# MCU_Display.net
KiCad netlist of a schematic drawn in Altium Designer
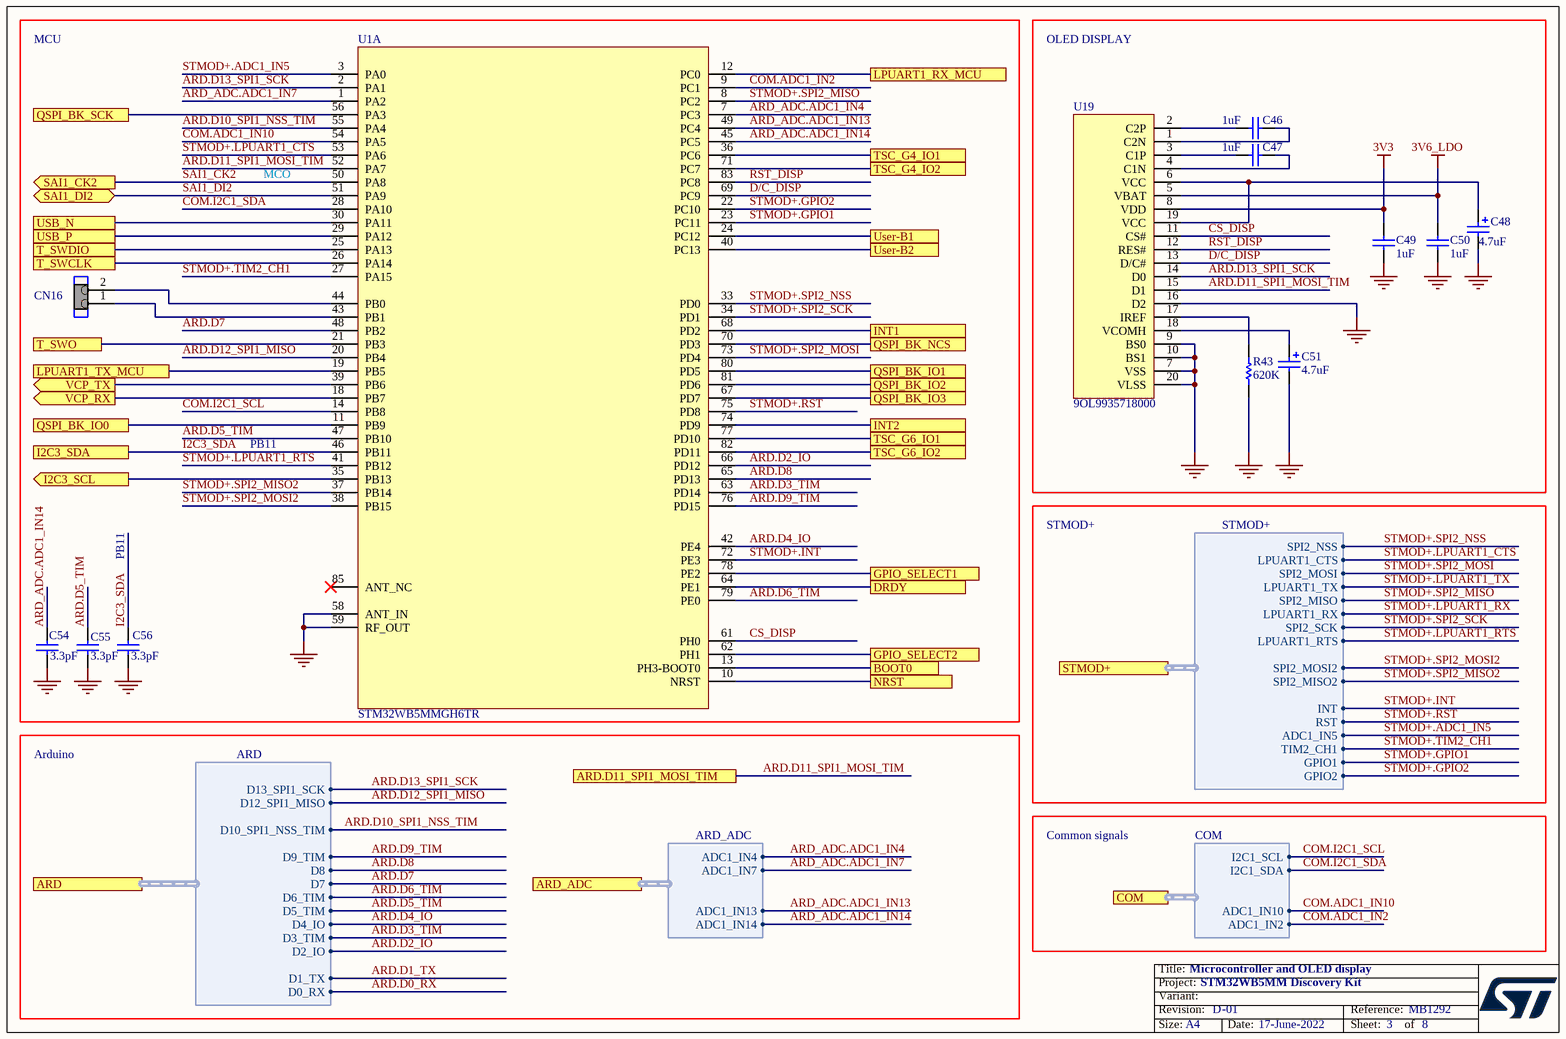
[diagram p0: MCU_Display.SchDoc]

(export (version "E")
  (design (tool "Eeschema 10.0.6"))
  (components
    (comp (ref "C46")
      (value "1uF")
      (footprint "C0603")
      (description "Capacitor, MLCC, 1uF, 16V, X5R, +/-10%, 0603, T=0,8mm")
      (fields
        (field (name "INTERNAL_PART_NUMBER") "MCD-00010")
        (field (name "MANUFACTURER_PART_NUMBER") "CC0603KRX5R7BB105")
      )
      (libsource (lib "MCD_PARTS_database") (part "Capacitor"))
    )
    (comp (ref "C47")
      (value "1uF")
      (footprint "C0603")
      (description "Capacitor, MLCC, 1uF, 16V, X5R, +/-10%, 0603, T=0,8mm")
      (fields
        (field (name "INTERNAL_PART_NUMBER") "MCD-00010")
        (field (name "MANUFACTURER_PART_NUMBER") "CC0603KRX5R7BB105")
      )
      (libsource (lib "MCD_PARTS_database") (part "Capacitor"))
    )
    (comp (ref "C48")
      (value "4.7uF")
      (footprint "CPOL_TAJ-A_1206_H180")
      (description "Capacitor, Tantalum, 4.7uF, 25V, 5.5ohms, 10%,pkg Type_A (3216 metric), T=1.6mm")
      (fields
        (field (name "INTERNAL_PART_NUMBER") "MCD-01043")
        (field (name "MANUFACTURER_PART_NUMBER") "293D475X9025A2TE3")
      )
      (libsource (lib "MCD_PARTS_database") (part "Cap_POL_TANA"))
    )
    (comp (ref "C49")
      (value "1uF")
      (footprint "C0603")
      (description "Capacitor, MLCC, 1uF, 16V, X5R, +/-10%, 0603, T=0,8mm")
      (fields
        (field (name "INTERNAL_PART_NUMBER") "MCD-00010")
        (field (name "MANUFACTURER_PART_NUMBER") "CC0603KRX5R7BB105")
      )
      (libsource (lib "MCD_PARTS_database") (part "Capacitor"))
    )
    (comp (ref "C50")
      (value "1uF")
      (footprint "C0603")
      (description "Capacitor, MLCC, 1uF, 16V, X5R, +/-10%, 0603, T=0,8mm")
      (fields
        (field (name "INTERNAL_PART_NUMBER") "MCD-00010")
        (field (name "MANUFACTURER_PART_NUMBER") "CC0603KRX5R7BB105")
      )
      (libsource (lib "MCD_PARTS_database") (part "Capacitor"))
    )
    (comp (ref "C51")
      (value "4.7uF")
      (footprint "CPOL_TAJ-A_1206_H180")
      (description "Capacitor, Tantalum, 4.7uF, 25V, 5.5ohms, 10%,pkg Type_A (3216 metric), T=1.6mm")
      (fields
        (field (name "INTERNAL_PART_NUMBER") "MCD-01043")
        (field (name "MANUFACTURER_PART_NUMBER") "293D475X9025A2TE3")
      )
      (libsource (lib "MCD_PARTS_database") (part "Cap_POL_TANA"))
    )
    (comp (ref "C54")
      (value "3.3pF")
      (footprint "C0201_H0P3")
      (description "Capacitor, MLCC, 3.3pF, 50V, NPO, +-0.05pF, 0201, T=0.3mm\".")
      (fields (field (name "INTERNAL_PART_NUMBER") "MCD-02284") (field (name "MANUFACTURER") "MURATA"))
      (libsource (lib "MCD_PARTS_database") (part "Capacitor"))
    )
    (comp (ref "C55")
      (value "3.3pF")
      (footprint "C0201_H0P3")
      (description "Capacitor, MLCC, 3.3pF, 50V, NPO, +-0.05pF, 0201, T=0.3mm\".")
      (fields (field (name "INTERNAL_PART_NUMBER") "MCD-02284") (field (name "MANUFACTURER") "MURATA"))
      (libsource (lib "MCD_PARTS_database") (part "Capacitor"))
    )
    (comp (ref "C56")
      (value "3.3pF")
      (footprint "C0201_H0P3")
      (description "Capacitor, MLCC, 3.3pF, 50V, NPO, +-0.05pF, 0201, T=0.3mm\".")
      (fields (field (name "INTERNAL_PART_NUMBER") "MCD-02284") (field (name "MANUFACTURER") "MURATA"))
      (libsource (lib "MCD_PARTS_database") (part "Capacitor"))
    )
    (comp (ref "CN16")
      (value "Jumper_Header1.27 2x1 Fitted")
      (footprint "CON_WP_707-2-02-2-20-00")
      (description "Header, 2x1, 1.27mm, RA, TH, T=3.05mm/1.27mm")
      (fields (field (name "INTERNAL_PART_NUMBER") "MCD-01428") (field (name "MANUFACTURER") "W&P PRODUCTS"))
      (libsource (lib "MCD_PARTS_database") (part "Jumper_Header1.27 2x1 Fitted"))
    )
    (comp (ref "R43")
      (value "620K")
      (footprint "R0603")
      (description "Resistor,620K,0603,1%,1/10W")
      (fields
        (field (name "INTERNAL_PART_NUMBER") "MCD-00506")
        (field (name "MANUFACTURER_PART_NUMBER") "RC0603FR-07620KL")
      )
      (libsource (lib "MCD_PARTS_database") (part "Resistor"))
    )
    (comp (ref "U1")
      (value "STM32WB5MMGH6TR")
      (footprint "MOD_DORY_STM_86P_7P3X11_H1P342")
      (description "STM32 BLE module based on STM32WB55")
      (fields
        (field (name "INTERNAL_PART_NUMBER") "MCD-01965")
        (field (name "MANUFACTURER") "STMICROELECTRONICS")
      )
      (libsource (lib "MCD_PARTS_database") (part "STM32WB5MMGH6TR"))
    )
    (comp (ref "U19")
      (value "9OL9935718000")
      (footprint "OLED_RITDISPLAY_9OL9935718000")
      (description "128*64 Dots 20-pin OLED display")
      (fields (field (name "INTERNAL_PART_NUMBER") "MCD-01925") (field (name "MANUFACTURER") "RITDISPLAY"))
      (libsource (lib "MCD_PARTS_database") (part "OLED_RITDISPLAY_9OL9935718000"))
    )
  )
  (nets
    (net (code "7") (name "/ARD.D2_IO") (class "Default")
      (node (ref "U1") (pin "66") (pinfunction "PD12_66") (pintype "passive"))
    )
    (net (code "8") (name "/ARD.D3_TIM") (class "Default")
      (node (ref "U1") (pin "63") (pinfunction "PD14_63") (pintype "passive"))
    )
    (net (code "9") (name "/ARD.D4_IO") (class "Default")
      (node (ref "U1") (pin "42") (pinfunction "PE4_42") (pintype "passive"))
    )
    (net (code "10") (name "/ARD.D5_TIM") (class "Default")
      (node (ref "C55") (pin "2") (pinfunction "2_2") (pintype "passive"))
      (node (ref "U1") (pin "47") (pinfunction "PB10_47") (pintype "passive"))
    )
    (net (code "11") (name "/ARD.D6_TIM") (class "Default")
      (node (ref "U1") (pin "79") (pinfunction "PE0_79") (pintype "passive"))
    )
    (net (code "12") (name "/ARD.D7") (class "Default")
      (node (ref "U1") (pin "48") (pinfunction "PB2_48") (pintype "passive"))
    )
    (net (code "13") (name "/ARD.D8") (class "Default")
      (node (ref "U1") (pin "65") (pinfunction "PD13_65") (pintype "passive"))
    )
    (net (code "14") (name "/ARD.D9_TIM") (class "Default")
      (node (ref "U1") (pin "76") (pinfunction "PD15_76") (pintype "passive"))
    )
    (net (code "15") (name "/ARD.D10_SPI1_NSS_TIM") (class "Default")
      (node (ref "U1") (pin "55") (pinfunction "PA4_55") (pintype "passive"))
    )
    (net (code "16") (name "/ARD.D11_SPI1_MOSI_TIM") (class "Default")
      (node (ref "U1") (pin "52") (pinfunction "PA7_52") (pintype "passive"))
      (node (ref "U19") (pin "15") (pinfunction "D1_15") (pintype "passive"))
    )
    (net (code "17") (name "/ARD.D12_SPI1_MISO") (class "Default")
      (node (ref "U1") (pin "20") (pinfunction "PB4_20") (pintype "passive"))
    )
    (net (code "18") (name "/ARD.D13_SPI1_SCK") (class "Default")
      (node (ref "U1") (pin "2") (pinfunction "PA1_2") (pintype "passive"))
      (node (ref "U19") (pin "14") (pinfunction "D0_14") (pintype "passive"))
    )
    (net (code "19") (name "/ARD_ADC.ADC1_IN4") (class "Default")
      (node (ref "U1") (pin "7") (pinfunction "PC3_7") (pintype "passive"))
    )
    (net (code "20") (name "/ARD_ADC.ADC1_IN7") (class "Default")
      (node (ref "U1") (pin "1") (pinfunction "PA2_1") (pintype "passive"))
    )
    (net (code "21") (name "/ARD_ADC.ADC1_IN13") (class "Default")
      (node (ref "U1") (pin "49") (pinfunction "PC4_49") (pintype "passive"))
    )
    (net (code "22") (name "/ARD_ADC.ADC1_IN14") (class "Default")
      (node (ref "C54") (pin "1") (pinfunction "1_1") (pintype "passive"))
      (node (ref "U1") (pin "45") (pinfunction "PC5_45") (pintype "passive"))
    )
    (net (code "23") (name "/BOOT0") (class "Default")
      (node (ref "U1") (pin "13") (pinfunction "PH3-BOOT0_13") (pintype "passive"))
    )
    (net (code "24") (name "/COM.ADC1_IN2") (class "Default")
      (node (ref "U1") (pin "9") (pinfunction "PC1_9") (pintype "passive"))
    )
    (net (code "25") (name "/COM.ADC1_IN10") (class "Default")
      (node (ref "U1") (pin "54") (pinfunction "PA5_54") (pintype "passive"))
    )
    (net (code "26") (name "/COM.I2C1_SCL") (class "Default")
      (node (ref "U1") (pin "14") (pinfunction "PB8_14") (pintype "passive"))
    )
    (net (code "27") (name "/COM.I2C1_SDA") (class "Default")
      (node (ref "U1") (pin "28") (pinfunction "PA10_28") (pintype "passive"))
    )
    (net (code "28") (name "/CS_DISP") (class "Default")
      (node (ref "U1") (pin "61") (pinfunction "PH0_61") (pintype "passive"))
      (node (ref "U19") (pin "11") (pinfunction "CS#_11") (pintype "passive"))
    )
    (net (code "29") (name "/DRDY") (class "Default")
      (node (ref "U1") (pin "64") (pinfunction "PE1_64") (pintype "passive"))
    )
    (net (code "30") (name "/D{slash}C_DISP") (class "Default")
      (node (ref "U1") (pin "69") (pinfunction "PC9_69") (pintype "passive"))
      (node (ref "U19") (pin "13") (pinfunction "D/C#_13") (pintype "passive"))
    )
    (net (code "31") (name "/GPIO_SELECT1") (class "Default")
      (node (ref "U1") (pin "78") (pinfunction "PE2_78") (pintype "passive"))
    )
    (net (code "32") (name "/GPIO_SELECT2") (class "Default")
      (node (ref "U1") (pin "62") (pinfunction "PH1_62") (pintype "passive"))
    )
    (net (code "33") (name "/I2C3_SCL") (class "Default")
      (node (ref "U1") (pin "35") (pinfunction "PB13_35") (pintype "passive"))
    )
    (net (code "34") (name "/I2C3_SDA") (class "Default")
      (node (ref "C56") (pin "2") (pinfunction "2_2") (pintype "passive"))
      (node (ref "U1") (pin "46") (pinfunction "PB11_46") (pintype "passive"))
    )
    (net (code "35") (name "/INT1") (class "Default")
      (node (ref "U1") (pin "68") (pinfunction "PD2_68") (pintype "passive"))
    )
    (net (code "36") (name "/INT2") (class "Default")
      (node (ref "U1") (pin "74") (pinfunction "PD9_74") (pintype "passive"))
    )
    (net (code "37") (name "/LPUART1_RX_MCU") (class "Default")
      (node (ref "U1") (pin "12") (pinfunction "PC0_12") (pintype "passive"))
    )
    (net (code "38") (name "/LPUART1_TX_MCU") (class "Default")
      (node (ref "U1") (pin "19") (pinfunction "PB5_19") (pintype "passive"))
    )
    (net (code "39") (name "/NRST") (class "Default")
      (node (ref "U1") (pin "10") (pinfunction "NRST_10") (pintype "passive"))
    )
    (net (code "40") (name "/QSPI_BK_IO0") (class "Default")
      (node (ref "U1") (pin "11") (pinfunction "PB9_11") (pintype "passive"))
    )
    (net (code "41") (name "/QSPI_BK_IO1") (class "Default")
      (node (ref "U1") (pin "80") (pinfunction "PD5_80") (pintype "passive"))
    )
    (net (code "42") (name "/QSPI_BK_IO2") (class "Default")
      (node (ref "U1") (pin "81") (pinfunction "PD6_81") (pintype "passive"))
    )
    (net (code "43") (name "/QSPI_BK_IO3") (class "Default")
      (node (ref "U1") (pin "67") (pinfunction "PD7_67") (pintype "passive"))
    )
    (net (code "44") (name "/QSPI_BK_NCS") (class "Default")
      (node (ref "U1") (pin "70") (pinfunction "PD3_70") (pintype "passive"))
    )
    (net (code "45") (name "/QSPI_BK_SCK") (class "Default")
      (node (ref "U1") (pin "56") (pinfunction "PA3_56") (pintype "passive"))
    )
    (net (code "46") (name "/RST_DISP") (class "Default")
      (node (ref "U1") (pin "83") (pinfunction "PC8_83") (pintype "passive"))
      (node (ref "U19") (pin "12") (pinfunction "RES#_12") (pintype "passive"))
    )
    (net (code "47") (name "/SAI1_CK2") (class "Default")
      (node (ref "U1") (pin "50") (pinfunction "PA8_50") (pintype "passive"))
    )
    (net (code "48") (name "/SAI1_DI2") (class "Default")
      (node (ref "U1") (pin "51") (pinfunction "PA9_51") (pintype "passive"))
    )
    (net (code "49") (name "/STMOD+.ADC1_IN5") (class "Default")
      (node (ref "U1") (pin "3") (pinfunction "PA0_3") (pintype "passive"))
    )
    (net (code "50") (name "/STMOD+.GPIO1") (class "Default")
      (node (ref "U1") (pin "23") (pinfunction "PC11_23") (pintype "passive"))
    )
    (net (code "51") (name "/STMOD+.GPIO2") (class "Default")
      (node (ref "U1") (pin "22") (pinfunction "PC10_22") (pintype "passive"))
    )
    (net (code "52") (name "/STMOD+.INT") (class "Default")
      (node (ref "U1") (pin "72") (pinfunction "PE3_72") (pintype "passive"))
    )
    (net (code "53") (name "/STMOD+.LPUART1_CTS") (class "Default")
      (node (ref "U1") (pin "53") (pinfunction "PA6_53") (pintype "passive"))
    )
    (net (code "54") (name "/STMOD+.LPUART1_RTS") (class "Default")
      (node (ref "U1") (pin "41") (pinfunction "PB12_41") (pintype "passive"))
    )
    (net (code "57") (name "/STMOD+.RST") (class "Default")
      (node (ref "U1") (pin "75") (pinfunction "PD8_75") (pintype "passive"))
    )
    (net (code "58") (name "/STMOD+.SPI2_MISO") (class "Default")
      (node (ref "U1") (pin "8") (pinfunction "PC2_8") (pintype "passive"))
    )
    (net (code "59") (name "/STMOD+.SPI2_MISO2") (class "Default")
      (node (ref "U1") (pin "37") (pinfunction "PB14_37") (pintype "passive"))
    )
    (net (code "60") (name "/STMOD+.SPI2_MOSI") (class "Default")
      (node (ref "U1") (pin "73") (pinfunction "PD4_73") (pintype "passive"))
    )
    (net (code "61") (name "/STMOD+.SPI2_MOSI2") (class "Default")
      (node (ref "U1") (pin "38") (pinfunction "PB15_38") (pintype "passive"))
    )
    (net (code "62") (name "/STMOD+.SPI2_NSS") (class "Default")
      (node (ref "U1") (pin "33") (pinfunction "PD0_33") (pintype "passive"))
    )
    (net (code "63") (name "/STMOD+.SPI2_SCK") (class "Default")
      (node (ref "U1") (pin "34") (pinfunction "PD1_34") (pintype "passive"))
    )
    (net (code "64") (name "/STMOD+.TIM2_CH1") (class "Default")
      (node (ref "U1") (pin "27") (pinfunction "PA15_27") (pintype "passive"))
    )
    (net (code "65") (name "/TSC_G4_IO1") (class "Default")
      (node (ref "U1") (pin "36") (pinfunction "PC6_36") (pintype "passive"))
    )
    (net (code "66") (name "/TSC_G4_IO2") (class "Default")
      (node (ref "U1") (pin "71") (pinfunction "PC7_71") (pintype "passive"))
    )
    (net (code "67") (name "/TSC_G6_IO1") (class "Default")
      (node (ref "U1") (pin "77") (pinfunction "PD10_77") (pintype "passive"))
    )
    (net (code "68") (name "/TSC_G6_IO2") (class "Default")
      (node (ref "U1") (pin "82") (pinfunction "PD11_82") (pintype "passive"))
    )
    (net (code "69") (name "/T_SWCLK") (class "Default")
      (node (ref "U1") (pin "26") (pinfunction "PA14_26") (pintype "passive"))
    )
    (net (code "70") (name "/T_SWDIO") (class "Default")
      (node (ref "U1") (pin "25") (pinfunction "PA13_25") (pintype "passive"))
    )
    (net (code "71") (name "/T_SWO") (class "Default")
      (node (ref "U1") (pin "21") (pinfunction "PB3_21") (pintype "passive"))
    )
    (net (code "72") (name "/USB_N") (class "Default")
      (node (ref "U1") (pin "30") (pinfunction "PA11_30") (pintype "passive"))
    )
    (net (code "73") (name "/USB_P") (class "Default")
      (node (ref "U1") (pin "29") (pinfunction "PA12_29") (pintype "passive"))
    )
    (net (code "74") (name "/User-B1") (class "Default")
      (node (ref "U1") (pin "24") (pinfunction "PC12_24") (pintype "passive"))
    )
    (net (code "75") (name "/User-B2") (class "Default")
      (node (ref "U1") (pin "40") (pinfunction "PC13_40") (pintype "passive"))
    )
    (net (code "76") (name "/VCP_RX") (class "Default")
      (node (ref "U1") (pin "18") (pinfunction "PB7_18") (pintype "passive"))
    )
    (net (code "77") (name "/VCP_TX") (class "Default")
      (node (ref "U1") (pin "39") (pinfunction "PB6_39") (pintype "passive"))
    )
    (net (code "82") (name "3V3") (class "Default")
      (node (ref "C49") (pin "1") (pinfunction "1_1") (pintype "passive"))
      (node (ref "U19") (pin "8") (pinfunction "VDD_8") (pintype "passive"))
    )
    (net (code "83") (name "3V6_LDO") (class "Default")
      (node (ref "C50") (pin "1") (pinfunction "1_1") (pintype "passive"))
      (node (ref "U19") (pin "5") (pinfunction "VBAT_5") (pintype "passive"))
    )
    (net (code "84") (name "GND") (class "Default")
      (node (ref "C48") (pin "2") (pinfunction "2_2") (pintype "passive"))
      (node (ref "C49") (pin "2") (pinfunction "2_2") (pintype "passive"))
      (node (ref "C50") (pin "2") (pinfunction "2_2") (pintype "passive"))
      (node (ref "C51") (pin "2") (pinfunction "2_2") (pintype "passive"))
      (node (ref "C54") (pin "2") (pinfunction "2_2") (pintype "passive"))
      (node (ref "C55") (pin "1") (pinfunction "1_1") (pintype "passive"))
      (node (ref "C56") (pin "1") (pinfunction "1_1") (pintype "passive"))
      (node (ref "R43") (pin "1") (pinfunction "1_1") (pintype "passive"))
      (node (ref "U1") (pin "58") (pinfunction "ANT_IN_58") (pintype "passive"))
      (node (ref "U1") (pin "59") (pinfunction "RF_OUT_59") (pintype "passive"))
      (node (ref "U19") (pin "10") (pinfunction "BS1_10") (pintype "passive"))
      (node (ref "U19") (pin "16") (pinfunction "D2_16") (pintype "passive"))
      (node (ref "U19") (pin "20") (pinfunction "VLSS_20") (pintype "passive"))
      (node (ref "U19") (pin "7") (pinfunction "VSS_7") (pintype "passive"))
      (node (ref "U19") (pin "9") (pinfunction "BS0_9") (pintype "passive"))
    )
    (net (code "85") (name "Net-(C48-Pad1)") (class "Default")
      (node (ref "C48") (pin "1") (pinfunction "1_1") (pintype "passive"))
      (node (ref "U19") (pin "19") (pinfunction "VCC_19") (pintype "passive"))
      (node (ref "U19") (pin "6") (pinfunction "VCC_6") (pintype "passive"))
    )
    (net (code "86") (name "Net-(U1A-PB0)") (class "Default")
      (node (ref "CN16") (pin "2") (pinfunction "2_2") (pintype "passive"))
      (node (ref "U1") (pin "44") (pinfunction "PB0_44") (pintype "passive"))
    )
    (net (code "87") (name "Net-(U1A-PB1)") (class "Default")
      (node (ref "CN16") (pin "1") (pinfunction "1_1") (pintype "passive"))
      (node (ref "U1") (pin "43") (pinfunction "PB1_43") (pintype "passive"))
    )
    (net (code "88") (name "Net-(U19-C1N)") (class "Default")
      (node (ref "C47") (pin "2") (pinfunction "2_2") (pintype "passive"))
      (node (ref "U19") (pin "4") (pinfunction "C1N_4") (pintype "passive"))
    )
    (net (code "89") (name "Net-(U19-C1P)") (class "Default")
      (node (ref "C47") (pin "1") (pinfunction "1_1") (pintype "passive"))
      (node (ref "U19") (pin "3") (pinfunction "C1P_3") (pintype "passive"))
    )
    (net (code "90") (name "Net-(U19-C2N)") (class "Default")
      (node (ref "C46") (pin "2") (pinfunction "2_2") (pintype "passive"))
      (node (ref "U19") (pin "1") (pinfunction "C2N_1") (pintype "passive"))
    )
    (net (code "91") (name "Net-(U19-C2P)") (class "Default")
      (node (ref "C46") (pin "1") (pinfunction "1_1") (pintype "passive"))
      (node (ref "U19") (pin "2") (pinfunction "C2P_2") (pintype "passive"))
    )
    (net (code "92") (name "Net-(U19-IREF)") (class "Default")
      (node (ref "R43") (pin "2") (pinfunction "2_2") (pintype "passive"))
      (node (ref "U19") (pin "17") (pinfunction "IREF_17") (pintype "passive"))
    )
    (net (code "93") (name "Net-(U19-VCOMH)") (class "Default")
      (node (ref "C51") (pin "1") (pinfunction "1_1") (pintype "passive"))
      (node (ref "U19") (pin "18") (pinfunction "VCOMH_18") (pintype "passive"))
    )
    (net (code "94") (name "unconnected-(U1A-ANT_NC-Pad85)") (class "Default")
      (node (ref "U1") (pin "85") (pinfunction "ANT_NC_85") (pintype "passive+no_connect"))
    )
  )
)
